# Master.net
KiCad netlist of a schematic drawn in Altium Designer
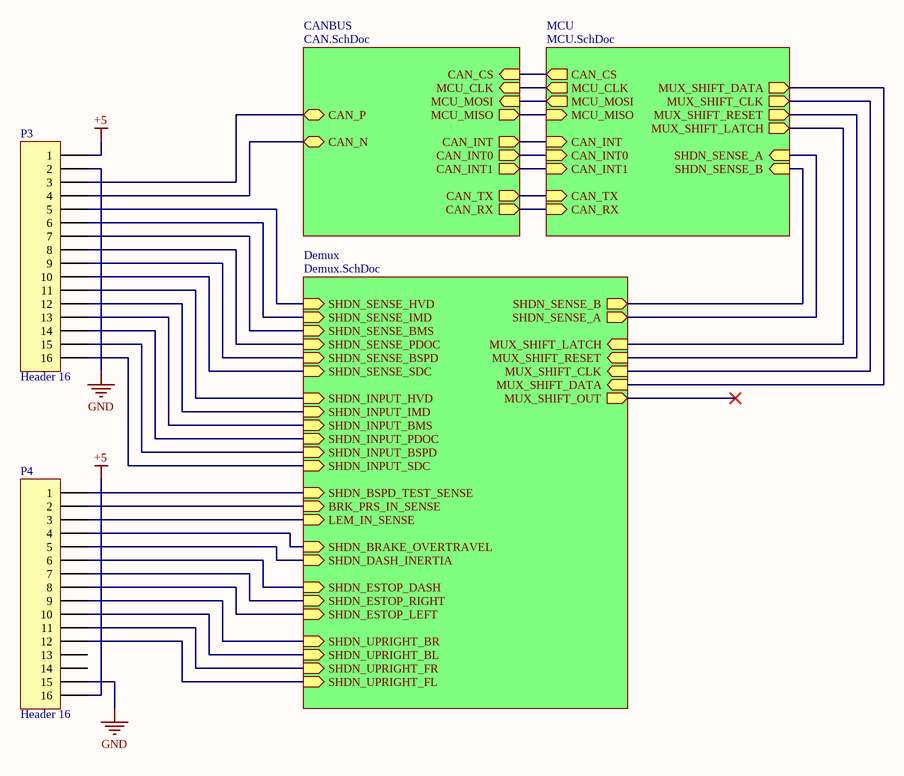
[diagram p0: Master.SchDoc]

(export (version "E")
  (design (tool "Eeschema 10.0.6"))
  (components
    (comp (ref "P3")
      (value "Header 16")
      (footprint "HDR1X16")
      (description "Header, 16-Pin")
      (fields (field (name "PUBLISHER") "Altium Limited"))
      (libsource (lib "Miscellaneous Connectors") (part "Header 16"))
    )
    (comp (ref "P4")
      (value "Header 16")
      (footprint "HDR1X16")
      (description "Header, 16-Pin")
      (fields (field (name "PUBLISHER") "Altium Limited"))
      (libsource (lib "Miscellaneous Connectors") (part "Header 16"))
    )
  )
  (nets
    (net (code "1") (name "+5") (class "Default")
      (node (ref "P3") (pin "1") (pinfunction "1_1") (pintype "passive"))
      (node (ref "P4") (pin "16") (pinfunction "16_16") (pintype "passive"))
    )
    (net (code "2") (name "/BRK_PRS_IN_SENSE") (class "Default")
      (node (ref "P4") (pin "2") (pinfunction "2_2") (pintype "passive"))
    )
    (net (code "7") (name "/CAN_N") (class "Default")
      (node (ref "P3") (pin "4") (pinfunction "4_4") (pintype "passive"))
    )
    (net (code "8") (name "/CAN_P") (class "Default")
      (node (ref "P3") (pin "3") (pinfunction "3_3") (pintype "passive"))
    )
    (net (code "11") (name "/LEM_IN_SENSE") (class "Default")
      (node (ref "P4") (pin "3") (pinfunction "3_3") (pintype "passive"))
    )
    (net (code "20") (name "/SHDN_BRAKE_OVERTRAVEL") (class "Default")
      (node (ref "P4") (pin "4") (pinfunction "4_4") (pintype "passive"))
    )
    (net (code "21") (name "/SHDN_BSPD_TEST_SENSE") (class "Default")
      (node (ref "P4") (pin "1") (pinfunction "1_1") (pintype "passive"))
    )
    (net (code "22") (name "/SHDN_DASH_INERTIA") (class "Default")
      (node (ref "P4") (pin "5") (pinfunction "5_5") (pintype "passive"))
    )
    (net (code "23") (name "/SHDN_ESTOP_DASH") (class "Default")
      (node (ref "P4") (pin "6") (pinfunction "6_6") (pintype "passive"))
    )
    (net (code "24") (name "/SHDN_ESTOP_LEFT") (class "Default")
      (node (ref "P4") (pin "8") (pinfunction "8_8") (pintype "passive"))
    )
    (net (code "25") (name "/SHDN_ESTOP_RIGHT") (class "Default")
      (node (ref "P4") (pin "7") (pinfunction "7_7") (pintype "passive"))
    )
    (net (code "26") (name "/SHDN_INPUT_BMS") (class "Default")
      (node (ref "P3") (pin "13") (pinfunction "13_13") (pintype "passive"))
    )
    (net (code "27") (name "/SHDN_INPUT_BSPD") (class "Default")
      (node (ref "P3") (pin "15") (pinfunction "15_15") (pintype "passive"))
    )
    (net (code "28") (name "/SHDN_INPUT_HVD") (class "Default")
      (node (ref "P3") (pin "11") (pinfunction "11_11") (pintype "passive"))
    )
    (net (code "29") (name "/SHDN_INPUT_IMD") (class "Default")
      (node (ref "P3") (pin "12") (pinfunction "12_12") (pintype "passive"))
    )
    (net (code "30") (name "/SHDN_INPUT_PDOC") (class "Default")
      (node (ref "P3") (pin "14") (pinfunction "14_14") (pintype "passive"))
    )
    (net (code "31") (name "/SHDN_INPUT_SDC") (class "Default")
      (node (ref "P3") (pin "16") (pinfunction "16_16") (pintype "passive"))
    )
    (net (code "34") (name "/SHDN_SENSE_BMS") (class "Default")
      (node (ref "P3") (pin "7") (pinfunction "7_7") (pintype "passive"))
    )
    (net (code "35") (name "/SHDN_SENSE_BSPD") (class "Default")
      (node (ref "P3") (pin "9") (pinfunction "9_9") (pintype "passive"))
    )
    (net (code "36") (name "/SHDN_SENSE_HVD") (class "Default")
      (node (ref "P3") (pin "5") (pinfunction "5_5") (pintype "passive"))
    )
    (net (code "37") (name "/SHDN_SENSE_IMD") (class "Default")
      (node (ref "P3") (pin "6") (pinfunction "6_6") (pintype "passive"))
    )
    (net (code "38") (name "/SHDN_SENSE_PDOC") (class "Default")
      (node (ref "P3") (pin "8") (pinfunction "8_8") (pintype "passive"))
    )
    (net (code "39") (name "/SHDN_SENSE_SDC") (class "Default")
      (node (ref "P3") (pin "10") (pinfunction "10_10") (pintype "passive"))
    )
    (net (code "40") (name "/SHDN_UPRIGHT_BL") (class "Default")
      (node (ref "P4") (pin "10") (pinfunction "10_10") (pintype "passive"))
    )
    (net (code "41") (name "/SHDN_UPRIGHT_BR") (class "Default")
      (node (ref "P4") (pin "9") (pinfunction "9_9") (pintype "passive"))
    )
    (net (code "42") (name "/SHDN_UPRIGHT_FL") (class "Default")
      (node (ref "P4") (pin "12") (pinfunction "12_12") (pintype "passive"))
    )
    (net (code "43") (name "/SHDN_UPRIGHT_FR") (class "Default")
      (node (ref "P4") (pin "11") (pinfunction "11_11") (pintype "passive"))
    )
    (net (code "44") (name "GND") (class "Default")
      (node (ref "P3") (pin "2") (pinfunction "2_2") (pintype "passive"))
      (node (ref "P4") (pin "15") (pinfunction "15_15") (pintype "passive"))
    )
    (net (code "45") (name "unconnected-(P4-Pad13)") (class "Default")
      (node (ref "P4") (pin "13") (pinfunction "13_13") (pintype "passive"))
    )
    (net (code "46") (name "unconnected-(P4-Pad14)") (class "Default")
      (node (ref "P4") (pin "14") (pinfunction "14_14") (pintype "passive"))
    )
  )
)
